# Relay_Driver.net
KiCad netlist of a schematic drawn in Altium Designer
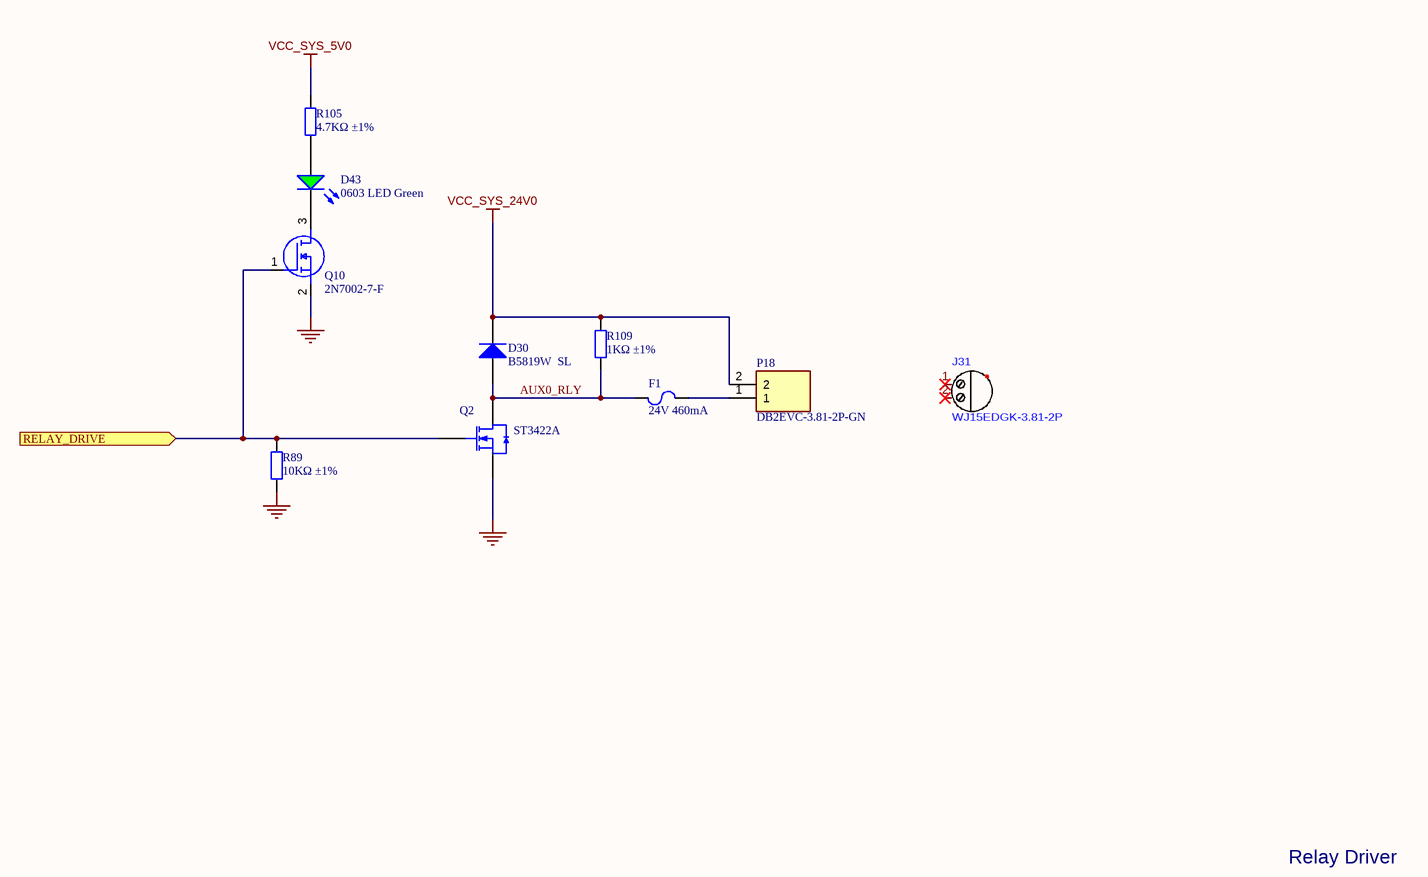
[diagram p0: Relay_Driver.SchDoc]

(export (version "E")
  (design (tool "Eeschema 10.0.6"))
  (components
    (comp (ref "D30")
      (value "B5819W  SL")
      (footprint "SOD-123")
      (description "40V 600mV@1A 1A SOD-123 Schottky Barrier Diodes (SBD) ROHS")
      (fields
        (field (name "MANUFACTURER PART NUMBER") "B5819W SL")
        (field (name "MANUFACTURER") "Jiangsu Changjing Electronics Technology Co., Ltd.")
      )
      (libsource (lib "Sienci_Labs") (part "B5819W  SL"))
    )
    (comp (ref "D43")
      (value "0603 LED Green")
      (footprint "0603_LED_S1 - GREEN")
      (description "20mA -40℃~+85℃ 515nm~530nm Emerald 120° 60mW 0603 Light Emitting Diodes (LED) ROHS")
      (fields (field (name "MANUFACTURER PART NUMBER") "MHT192UGCT") (field (name "MANUFACTURER") "MEIHUA"))
      (libsource (lib "Sienci_Labs") (part "MHT192UGCT"))
    )
    (comp (ref "F1")
      (value "24V 460mA")
      (footprint "1206_C")
      (description "24V 200mA 100A 460mA - Resettable Fuses ROHS")
      (fields
        (field (name "MANUFACTURER") "Jinrui Electronic Materials Co.")
        (field (name "PARTNUMBER") "JK-nSMD020-24")
      )
      (libsource (lib "PrintNC_GRBLHAL_Breakout") (part "JK-nSMD050-24"))
    )
    (comp (ref "J31")
      (value "WJ15EDGK-3.81-2P")
      (description "2 1 3.81mm Green Plug P=3.81mm Pluggable System Terminal Block ROHS")
      (fields (field (name "MANUFACTURER") "Ningbo"))
      (libsource (lib "Sienci_Labs") (part "WJ15EDGK-3.81-2P"))
    )
    (comp (ref "P18")
      (value "DB2EVC-3.81-2P-GN")
      (footprint "CONN-TH_5P-P3.81_DB2EVC-3.81-2p")
      (description "3.81mm Green Board Edge/Receptacle-Close Push-Pull,P=3.81mm Pluggable System Terminal Block ROHS")
      (fields (field (name "MANUFACTURER") "DIBO"))
      (libsource (lib "Sienci_Labs") (part "DB2EVC-3.81-2P-GN"))
    )
    (comp (ref "Q2")
      (value "ST3422A")
      (footprint "SOT-23-3L")
      (fields (field (name "MANUFACTURER") "STANSON Tech."))
      (libsource (lib "Sienci_Labs") (part "ST3422A"))
    )
    (comp (ref "Q10")
      (value "2N7002-7-F")
      (footprint "SOT-23(SOT-23-3)")
      (description "60V 115mA 7.5Ω@5V,50mA 370mW N Channel SOT-23 MOSFETs ROHS")
      (fields (field (name "MANUFACTURER") "Diodes Inc.") (field (name "MOUSER PART NUMBER") "621-2N7002-F"))
      (libsource (lib "Sienci_Labs") (part "2N7002-7-F"))
    )
    (comp (ref "R89")
      (value "10KΩ ±1%")
      (footprint "0402_R")
      (description "Chip resistor")
      (fields
        (field (name "MANUFACTURER") "Uniroyal Elec")
        (field (name "MANUFACTURER PART NUMBER") "0402WGF1002TCE")
      )
      (libsource (lib "Sienci_Labs") (part "0402 10K (1002) 1%"))
    )
    (comp (ref "R105")
      (value "4.7KΩ ±1%")
      (footprint "0402_R")
      (description "Chip resistor")
      (fields
        (field (name "MANUFACTURER") "Uniroyal Elec")
        (field (name "MANUFACTURER PART NUMBER") "0402WGF4701TCE")
      )
      (libsource (lib "Sienci_Labs") (part "0402 4.7K (4701) 1%"))
    )
    (comp (ref "R109")
      (value "1KΩ ±1%")
      (footprint "0603_R")
      (description "Chip resistor")
      (fields (field (name "MANUFACTURER") "Uniroyal Elec") (field (name "POWER") "1/10W"))
      (libsource (lib "Sienci_Labs") (part "0603 1K (1001) 1%"))
    )
  )
  (nets
    (net (code "1") (name "/AUX0_RLY") (class "Default")
      (node (ref "D30") (pin "1") (pinfunction "A_1") (pintype "passive"))
      (node (ref "F1") (pin "2") (pinfunction "2_2") (pintype "passive"))
      (node (ref "Q2") (pin "3") (pinfunction "D_3") (pintype "passive"))
      (node (ref "R109") (pin "1") (pinfunction "1_1") (pintype "passive"))
    )
    (net (code "2") (name "/RELAY_DRIVE") (class "Default")
      (node (ref "Q10") (pin "1") (pinfunction "G_1") (pintype "passive"))
      (node (ref "Q2") (pin "1") (pinfunction "G_1") (pintype "passive"))
      (node (ref "R89") (pin "2") (pinfunction "2_2") (pintype "passive"))
    )
    (net (code "3") (name "GND") (class "Default")
      (node (ref "Q10") (pin "2") (pinfunction "S_2") (pintype "passive"))
      (node (ref "Q2") (pin "2") (pinfunction "S_2") (pintype "passive"))
      (node (ref "R89") (pin "1") (pinfunction "1_1") (pintype "passive"))
    )
    (net (code "4") (name "Net-(D43-PadA)") (class "Default")
      (node (ref "D43") (pin "A") (pinfunction "A_A") (pintype "passive"))
      (node (ref "R105") (pin "1") (pinfunction "1_1") (pintype "passive"))
    )
    (net (code "5") (name "Net-(F1-Pad1)") (class "Default")
      (node (ref "F1") (pin "1") (pinfunction "1_1") (pintype "passive"))
      (node (ref "P18") (pin "1") (pinfunction "1_1") (pintype "passive"))
    )
    (net (code "6") (name "Net-(Q10-D)") (class "Default")
      (node (ref "D43") (pin "K") (pinfunction "K_K") (pintype "passive"))
      (node (ref "Q10") (pin "3") (pinfunction "D_3") (pintype "passive"))
    )
    (net (code "7") (name "VCC_SYS_5V0") (class "Default")
      (node (ref "R105") (pin "2") (pinfunction "2_2") (pintype "passive"))
    )
    (net (code "8") (name "VCC_SYS_24V0") (class "Default")
      (node (ref "D30") (pin "2") (pinfunction "K_2") (pintype "passive"))
      (node (ref "P18") (pin "2") (pinfunction "2_2") (pintype "passive"))
      (node (ref "R109") (pin "2") (pinfunction "2_2") (pintype "passive"))
    )
    (net (code "9") (name "unconnected-(J31-Pad1)") (class "Default")
      (node (ref "J31") (pin "1") (pinfunction "1_1") (pintype "passive+no_connect"))
    )
    (net (code "10") (name "unconnected-(J31-Pad2)") (class "Default")
      (node (ref "J31") (pin "2") (pinfunction "2_2") (pintype "passive+no_connect"))
    )
  )
)
